# differential-buffer.net
KiCad netlist of a schematic drawn in EAGLE
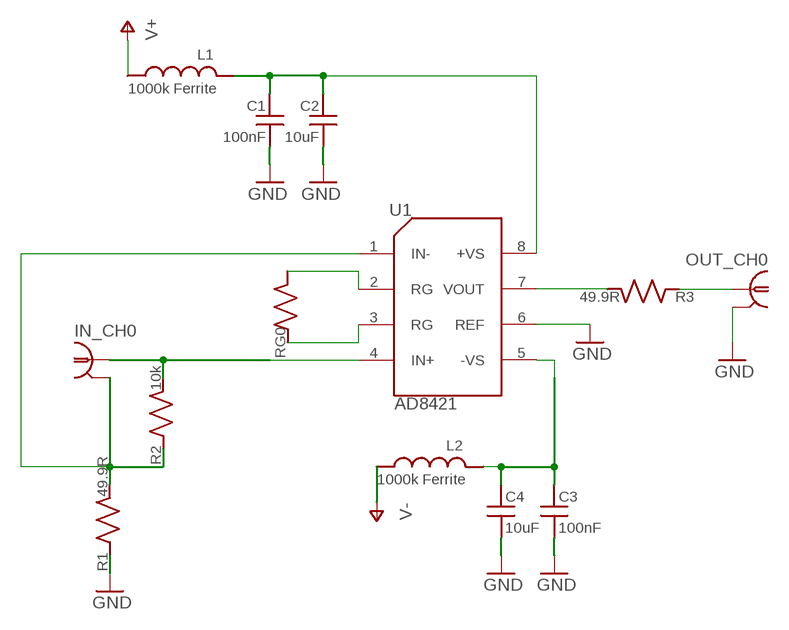
[diagram p0: schematic, sheet 1]

(export (version "E")
  (design (tool "Eeschema 10.0.6"))
  (components
    (comp (ref "C1")
      (value "100nF")
      (footprint "eagle-import:C_MLCC_0603")
      (fields (field (name "PARTNO") "1276-1936-1-ND"))
      (libsource (lib "eagle-import") (part "C_MLCC_SMDCMLCC_0603"))
    )
    (comp (ref "C2")
      (value "10uF")
      (footprint "eagle-import:C_MLCC_0805")
      (fields (field (name "PARTNO") "445-14417-1-ND"))
      (libsource (lib "eagle-import") (part "C_MLCC_SMDCMLCC_0805"))
    )
    (comp (ref "C3")
      (value "100nF")
      (footprint "eagle-import:C_MLCC_0603")
      (fields (field (name "PARTNO") "1276-1936-1-ND"))
      (libsource (lib "eagle-import") (part "C_MLCC_SMDCMLCC_0603"))
    )
    (comp (ref "C4")
      (value "10uF")
      (footprint "eagle-import:C_MLCC_0805")
      (fields (field (name "PARTNO") "445-14417-1-ND"))
      (libsource (lib "eagle-import") (part "C_MLCC_SMDCMLCC_0805"))
    )
    (comp (ref "IN_CH0")
      (value "BNC-H")
      (footprint "eagle-import:BNC90")
      (fields (field (name "PARTNO") "A32260-ND"))
      (libsource (lib "eagle-import") (part "BNC-H"))
    )
    (comp (ref "L1")
      (value "1000k Ferrite")
      (footprint "eagle-import:L_FERRITE_0603")
      (fields (field (name "PARTNO") "445-1548-1-ND"))
      (libsource (lib "eagle-import") (part "L_FERRITE_SMDLFERRITE_0603"))
    )
    (comp (ref "L2")
      (value "1000k Ferrite")
      (footprint "eagle-import:L_FERRITE_0603")
      (fields (field (name "PARTNO") "445-1548-1-ND"))
      (libsource (lib "eagle-import") (part "L_FERRITE_SMDLFERRITE_0603"))
    )
    (comp (ref "OUT_CH0")
      (value "BNC-H")
      (footprint "eagle-import:BNC90")
      (libsource (lib "eagle-import") (part "connector-jqi_BNC-H"))
    )
    (comp (ref "R1")
      (value "49.9R")
      (footprint "eagle-import:R_0603")
      (libsource (lib "eagle-import") (part "jqi_passives_R_SMDR0603"))
    )
    (comp (ref "R2")
      (value "10k")
      (footprint "eagle-import:R_0603")
      (fields (field (name "PARTNO") "TNP10.0KAACT-ND"))
      (libsource (lib "eagle-import") (part "R_SMDR0603"))
    )
    (comp (ref "R3")
      (value "49.9R")
      (footprint "eagle-import:R_0603")
      (libsource (lib "eagle-import") (part "jqi_passives_R_SMDR0603"))
    )
    (comp (ref "RG0")
      (value "R_SMDR0402")
      (footprint "eagle-import:R_0402")
      (libsource (lib "eagle-import") (part "jqi_passives_R_SMDR0402"))
    )
    (comp (ref "U1")
      (value "AD8421")
      (footprint "eagle-import:SOIC-8")
      (libsource (lib "eagle-import") (part "AD8421"))
    )
  )
  (nets
    (net (code "1") (name "GND") (class "Default")
      (node (ref "C1") (pin "P$2") (pinfunction "2_P$2") (pintype "passive"))
      (node (ref "C2") (pin "P$2") (pinfunction "2_P$2") (pintype "passive"))
      (node (ref "C3") (pin "P$2") (pinfunction "2_P$2") (pintype "passive"))
      (node (ref "C4") (pin "P$2") (pinfunction "2_P$2") (pintype "passive"))
      (node (ref "OUT_CH0") (pin "2") (pinfunction "2_2") (pintype "passive"))
      (node (ref "R1") (pin "P$1") (pinfunction "1_P$1") (pintype "passive"))
      (node (ref "U1") (pin "6") (pinfunction "REF_6") (pintype "bidirectional"))
    )
    (net (code "2") (name "Net-(C1-1)") (class "Default")
      (node (ref "C1") (pin "P$1") (pinfunction "1_P$1") (pintype "passive"))
      (node (ref "C2") (pin "P$1") (pinfunction "1_P$1") (pintype "passive"))
      (node (ref "L1") (pin "P$1") (pinfunction "1_P$1") (pintype "passive"))
      (node (ref "U1") (pin "8") (pinfunction "+VS_8") (pintype "bidirectional"))
    )
    (net (code "3") (name "Net-(C3-1)") (class "Default")
      (node (ref "C3") (pin "P$1") (pinfunction "1_P$1") (pintype "passive"))
      (node (ref "C4") (pin "P$1") (pinfunction "1_P$1") (pintype "passive"))
      (node (ref "L2") (pin "P$1") (pinfunction "1_P$1") (pintype "passive"))
      (node (ref "U1") (pin "5") (pinfunction "-VS_5") (pintype "bidirectional"))
    )
    (net (code "4") (name "Net-(R1-2)") (class "Default")
      (node (ref "IN_CH0") (pin "2") (pinfunction "2_2") (pintype "passive"))
      (node (ref "R1") (pin "P$2") (pinfunction "2_P$2") (pintype "passive"))
      (node (ref "R2") (pin "P$1") (pinfunction "1_P$1") (pintype "passive"))
      (node (ref "U1") (pin "1") (pinfunction "IN-_1") (pintype "bidirectional"))
    )
    (net (code "5") (name "Net-(R2-2)") (class "Default")
      (node (ref "IN_CH0") (pin "1") (pinfunction "1_1") (pintype "passive"))
      (node (ref "R2") (pin "P$2") (pinfunction "2_P$2") (pintype "passive"))
      (node (ref "U1") (pin "4") (pinfunction "IN+_4") (pintype "bidirectional"))
    )
    (net (code "6") (name "Net-(R3-1)") (class "Default")
      (node (ref "OUT_CH0") (pin "1") (pinfunction "1_1") (pintype "passive"))
      (node (ref "R3") (pin "P$1") (pinfunction "1_P$1") (pintype "passive"))
    )
    (net (code "7") (name "Net-(R3-2)") (class "Default")
      (node (ref "R3") (pin "P$2") (pinfunction "2_P$2") (pintype "passive"))
      (node (ref "U1") (pin "7") (pinfunction "VOUT_7") (pintype "bidirectional"))
    )
    (net (code "8") (name "Net-(RG0-1)") (class "Default")
      (node (ref "RG0") (pin "P$1") (pinfunction "1_P$1") (pintype "passive"))
      (node (ref "U1") (pin "3") (pinfunction "RG_3") (pintype "bidirectional"))
    )
    (net (code "9") (name "Net-(RG0-2)") (class "Default")
      (node (ref "RG0") (pin "P$2") (pinfunction "2_P$2") (pintype "passive"))
      (node (ref "U1") (pin "2") (pinfunction "RG_2") (pintype "bidirectional"))
    )
    (net (code "10") (name "V+") (class "Default")
      (node (ref "L1") (pin "P$2") (pinfunction "2_P$2") (pintype "passive"))
    )
    (net (code "11") (name "V-") (class "Default")
      (node (ref "L2") (pin "P$2") (pinfunction "2_P$2") (pintype "passive"))
    )
  )
)
